# led-cpu-rev1.net
KiCad netlist of a schematic drawn in EAGLE
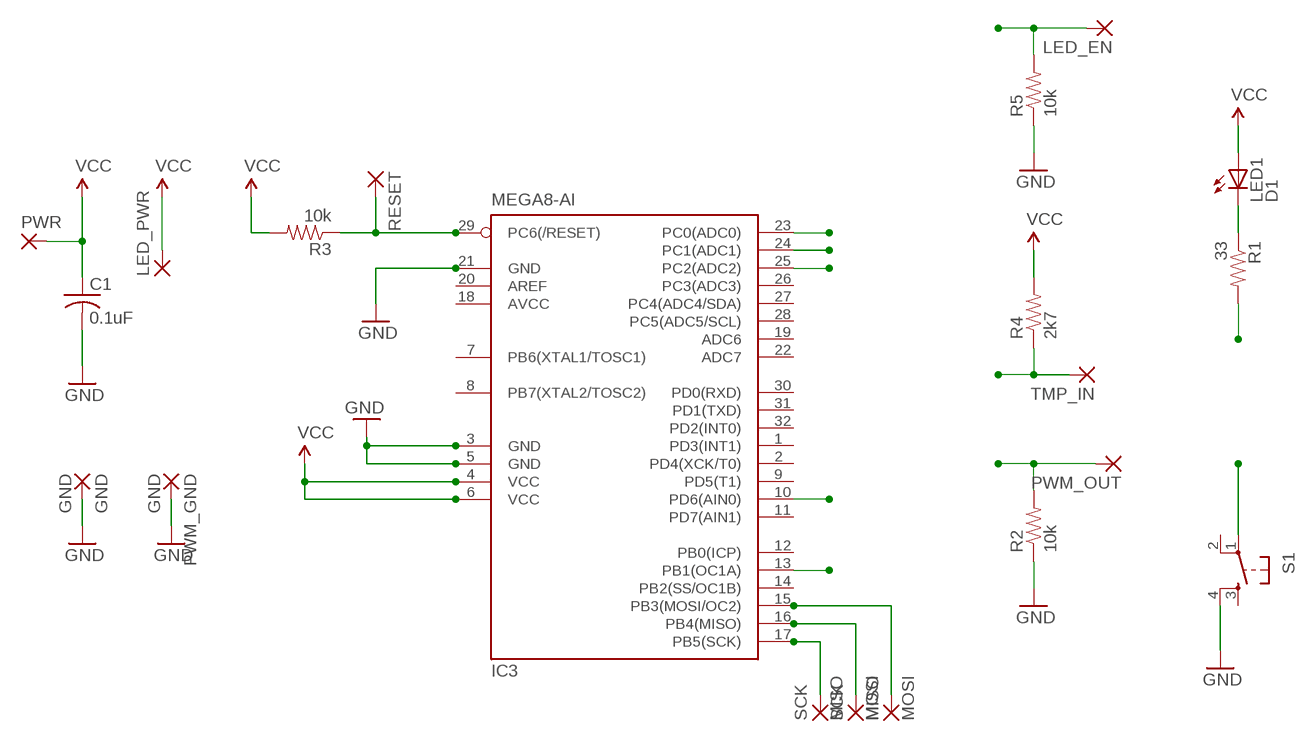
[diagram p0: schematic, sheet 1]

(export (version "E")
  (design (tool "Eeschema 10.0.6"))
  (components
    (comp (ref "C1")
      (value "0.1uF")
      (footprint "eagle-import:C1206")
      (libsource (lib "eagle-import") (part "C-USC1206"))
    )
    (comp (ref "GND")
      (value "GND")
      (footprint "eagle-import:SMD2,54-5,08")
      (libsource (lib "eagle-import") (part "SMD5"))
    )
    (comp (ref "IC3")
      (value "MEGA8-AI")
      (footprint "eagle-import:TQFP32-08")
      (fields (field (name "MPN") "ATMEGA8-16AU"))
      (libsource (lib "eagle-import") (part "MEGA8-AI"))
    )
    (comp (ref "LED1")
      (value "D1")
      (footprint "eagle-import:CHIPLED_1206")
      (libsource (lib "eagle-import") (part "LEDCHIPLED_1206"))
    )
    (comp (ref "LED_EN")
      (value "SMD5")
      (footprint "eagle-import:SMD2,54-5,08")
      (libsource (lib "eagle-import") (part "SMD5"))
    )
    (comp (ref "LED_PWR")
      (value "SMD5")
      (footprint "eagle-import:SMD2,54-5,08")
      (libsource (lib "eagle-import") (part "SMD5"))
    )
    (comp (ref "MISO")
      (value "MISO")
      (footprint "eagle-import:SMD1,27-2,54")
      (libsource (lib "eagle-import") (part "SMD2"))
    )
    (comp (ref "MOSI")
      (value "MOSI")
      (footprint "eagle-import:SMD1,27-2,54")
      (libsource (lib "eagle-import") (part "SMD2"))
    )
    (comp (ref "PWM_GND")
      (value "GND")
      (footprint "eagle-import:SMD2,54-5,08")
      (libsource (lib "eagle-import") (part "SMD5"))
    )
    (comp (ref "PWM_OUT")
      (value "SMD5")
      (footprint "eagle-import:SMD2,54-5,08")
      (libsource (lib "eagle-import") (part "SMD5"))
    )
    (comp (ref "PWR")
      (value "SMD5")
      (footprint "eagle-import:SMD2,54-5,08")
      (libsource (lib "eagle-import") (part "SMD5"))
    )
    (comp (ref "R1")
      (value "33")
      (footprint "eagle-import:1206")
      (libsource (lib "eagle-import") (part "RESISTOR1206"))
    )
    (comp (ref "R2")
      (value "10k")
      (footprint "eagle-import:1206")
      (libsource (lib "eagle-import") (part "RESISTOR1206"))
    )
    (comp (ref "R3")
      (value "10k")
      (footprint "eagle-import:1206")
      (libsource (lib "eagle-import") (part "RESISTOR1206"))
    )
    (comp (ref "R4")
      (value "2k7")
      (footprint "eagle-import:1206")
      (libsource (lib "eagle-import") (part "RESISTOR1206"))
    )
    (comp (ref "R5")
      (value "10k")
      (footprint "eagle-import:1206")
      (libsource (lib "eagle-import") (part "RESISTOR1206"))
    )
    (comp (ref "RESET")
      (value "SMD2")
      (footprint "eagle-import:SMD1,27-2,54")
      (libsource (lib "eagle-import") (part "SMD2"))
    )
    (comp (ref "S1")
      (value "TAC_SWITCHPTH")
      (footprint "eagle-import:TACTILE-PTH")
      (libsource (lib "eagle-import") (part "TAC_SWITCHPTH"))
    )
    (comp (ref "SCK")
      (value "SCK")
      (footprint "eagle-import:SMD1,27-2,54")
      (libsource (lib "eagle-import") (part "SMD2"))
    )
    (comp (ref "TMP_IN")
      (value "SMD5")
      (footprint "eagle-import:SMD2,54-5,08")
      (libsource (lib "eagle-import") (part "SMD5"))
    )
  )
  (nets
    (net (code "1") (name "/AVCC") (class "Default")
      (node (ref "IC3") (pin "18") (pinfunction "AVCC_18") (pintype "power_in"))
    )
    (net (code "2") (name "/LED_EN") (class "Default")
      (node (ref "IC3") (pin "25") (pinfunction "PC2(ADC2)_25") (pintype "bidirectional"))
      (node (ref "LED_EN") (pin "1") (pinfunction "P_1") (pintype "passive"))
      (node (ref "R5") (pin "2") (pinfunction "2_2") (pintype "passive"))
    )
    (net (code "3") (name "/PWM_OUT") (class "Default")
      (node (ref "IC3") (pin "10") (pinfunction "PD6(AIN0)_10") (pintype "bidirectional"))
      (node (ref "PWM_OUT") (pin "1") (pinfunction "P_1") (pintype "passive"))
      (node (ref "R2") (pin "2") (pinfunction "2_2") (pintype "passive"))
    )
    (net (code "4") (name "/PWR_LED") (class "Default")
      (node (ref "IC3") (pin "13") (pinfunction "PB1(OC1A)_13") (pintype "bidirectional"))
      (node (ref "R1") (pin "2") (pinfunction "2_2") (pintype "passive"))
    )
    (net (code "5") (name "/PWR_SW") (class "Default")
      (node (ref "IC3") (pin "24") (pinfunction "PC1(ADC1)_24") (pintype "bidirectional"))
      (node (ref "S1") (pin "1") (pinfunction "1_1") (pintype "passive"))
    )
    (net (code "6") (name "/TMP_IN") (class "Default")
      (node (ref "IC3") (pin "23") (pinfunction "PC0(ADC0)_23") (pintype "bidirectional"))
      (node (ref "R4") (pin "1") (pinfunction "1_1") (pintype "passive"))
      (node (ref "TMP_IN") (pin "1") (pinfunction "P_1") (pintype "passive"))
    )
    (net (code "7") (name "GND") (class "Default")
      (node (ref "C1") (pin "2") (pinfunction "2_2") (pintype "passive"))
      (node (ref "GND") (pin "1") (pinfunction "P_1") (pintype "passive"))
      (node (ref "IC3") (pin "21") (pinfunction "GND_21") (pintype "power_in"))
      (node (ref "IC3") (pin "3") (pinfunction "GND_3") (pintype "power_in"))
      (node (ref "IC3") (pin "5") (pinfunction "GND_5") (pintype "power_in"))
      (node (ref "PWM_GND") (pin "1") (pinfunction "P_1") (pintype "passive"))
      (node (ref "R2") (pin "1") (pinfunction "1_1") (pintype "passive"))
      (node (ref "R5") (pin "1") (pinfunction "1_1") (pintype "passive"))
      (node (ref "S1") (pin "4") (pinfunction "4_4") (pintype "passive"))
    )
    (net (code "8") (name "Net-(IC3-PB3(MOSI{slash}OC2))") (class "Default")
      (node (ref "IC3") (pin "15") (pinfunction "PB3(MOSI/OC2)_15") (pintype "bidirectional"))
      (node (ref "MOSI") (pin "1") (pinfunction "P_1") (pintype "passive"))
    )
    (net (code "9") (name "Net-(IC3-PB4(MISO))") (class "Default")
      (node (ref "IC3") (pin "16") (pinfunction "PB4(MISO)_16") (pintype "bidirectional"))
      (node (ref "MISO") (pin "1") (pinfunction "P_1") (pintype "passive"))
    )
    (net (code "10") (name "Net-(IC3-PB5(SCK))") (class "Default")
      (node (ref "IC3") (pin "17") (pinfunction "PB5(SCK)_17") (pintype "bidirectional"))
      (node (ref "SCK") (pin "1") (pinfunction "P_1") (pintype "passive"))
    )
    (net (code "11") (name "Net-(IC3-PC6({slash}RESET))") (class "Default")
      (node (ref "IC3") (pin "29") (pinfunction "PC6(/RESET)_29") (pintype "bidirectional"))
      (node (ref "R3") (pin "1") (pinfunction "1_1") (pintype "passive"))
      (node (ref "RESET") (pin "1") (pinfunction "P_1") (pintype "passive"))
    )
    (net (code "12") (name "Net-(LED1-PadC)") (class "Default")
      (node (ref "LED1") (pin "C") (pinfunction "C_C") (pintype "passive"))
      (node (ref "R1") (pin "1") (pinfunction "1_1") (pintype "passive"))
    )
    (net (code "13") (name "VCC") (class "Default")
      (node (ref "C1") (pin "1") (pinfunction "1_1") (pintype "passive"))
      (node (ref "IC3") (pin "4") (pinfunction "VCC_4") (pintype "power_in"))
      (node (ref "IC3") (pin "6") (pinfunction "VCC_6") (pintype "power_in"))
      (node (ref "LED1") (pin "A") (pinfunction "A_A") (pintype "passive"))
      (node (ref "LED_PWR") (pin "1") (pinfunction "P_1") (pintype "passive"))
      (node (ref "PWR") (pin "1") (pinfunction "P_1") (pintype "passive"))
      (node (ref "R3") (pin "2") (pinfunction "2_2") (pintype "passive"))
      (node (ref "R4") (pin "2") (pinfunction "2_2") (pintype "passive"))
    )
    (net (code "14") (name "unconnected-(IC3-ADC6-Pad19)") (class "Default")
      (node (ref "IC3") (pin "19") (pinfunction "ADC6_19") (pintype "bidirectional"))
    )
    (net (code "15") (name "unconnected-(IC3-ADC7-Pad22)") (class "Default")
      (node (ref "IC3") (pin "22") (pinfunction "ADC7_22") (pintype "bidirectional"))
    )
    (net (code "16") (name "unconnected-(IC3-AREF-Pad20)") (class "Default")
      (node (ref "IC3") (pin "20") (pinfunction "AREF_20") (pintype "passive"))
    )
    (net (code "17") (name "unconnected-(IC3-PB0(ICP)-Pad12)") (class "Default")
      (node (ref "IC3") (pin "12") (pinfunction "PB0(ICP)_12") (pintype "bidirectional"))
    )
    (net (code "18") (name "unconnected-(IC3-PB2(SS{slash}OC1B)-Pad14)") (class "Default")
      (node (ref "IC3") (pin "14") (pinfunction "PB2(SS/OC1B)_14") (pintype "bidirectional"))
    )
    (net (code "19") (name "unconnected-(IC3-PB6(XTAL1{slash}TOSC1)-Pad7)") (class "Default")
      (node (ref "IC3") (pin "7") (pinfunction "PB6(XTAL1/TOSC1)_7") (pintype "bidirectional"))
    )
    (net (code "20") (name "unconnected-(IC3-PB7(XTAL2{slash}TOSC2)-Pad8)") (class "Default")
      (node (ref "IC3") (pin "8") (pinfunction "PB7(XTAL2/TOSC2)_8") (pintype "bidirectional"))
    )
    (net (code "21") (name "unconnected-(IC3-PC3(ADC3)-Pad26)") (class "Default")
      (node (ref "IC3") (pin "26") (pinfunction "PC3(ADC3)_26") (pintype "bidirectional"))
    )
    (net (code "22") (name "unconnected-(IC3-PC4(ADC4{slash}SDA)-Pad27)") (class "Default")
      (node (ref "IC3") (pin "27") (pinfunction "PC4(ADC4/SDA)_27") (pintype "bidirectional"))
    )
    (net (code "23") (name "unconnected-(IC3-PC5(ADC5{slash}SCL)-Pad28)") (class "Default")
      (node (ref "IC3") (pin "28") (pinfunction "PC5(ADC5/SCL)_28") (pintype "bidirectional"))
    )
    (net (code "24") (name "unconnected-(IC3-PD0(RXD)-Pad30)") (class "Default")
      (node (ref "IC3") (pin "30") (pinfunction "PD0(RXD)_30") (pintype "bidirectional"))
    )
    (net (code "25") (name "unconnected-(IC3-PD1(TXD)-Pad31)") (class "Default")
      (node (ref "IC3") (pin "31") (pinfunction "PD1(TXD)_31") (pintype "bidirectional"))
    )
    (net (code "26") (name "unconnected-(IC3-PD2(INT0)-Pad32)") (class "Default")
      (node (ref "IC3") (pin "32") (pinfunction "PD2(INT0)_32") (pintype "bidirectional"))
    )
    (net (code "27") (name "unconnected-(IC3-PD3(INT1)-Pad1)") (class "Default")
      (node (ref "IC3") (pin "1") (pinfunction "PD3(INT1)_1") (pintype "bidirectional"))
    )
    (net (code "28") (name "unconnected-(IC3-PD4(XCK{slash}T0)-Pad2)") (class "Default")
      (node (ref "IC3") (pin "2") (pinfunction "PD4(XCK/T0)_2") (pintype "bidirectional"))
    )
    (net (code "29") (name "unconnected-(IC3-PD5(T1)-Pad9)") (class "Default")
      (node (ref "IC3") (pin "9") (pinfunction "PD5(T1)_9") (pintype "bidirectional"))
    )
    (net (code "30") (name "unconnected-(IC3-PD7(AIN1)-Pad11)") (class "Default")
      (node (ref "IC3") (pin "11") (pinfunction "PD7(AIN1)_11") (pintype "bidirectional"))
    )
    (net (code "31") (name "unconnected-(S1-Pad2)") (class "Default")
      (node (ref "S1") (pin "2") (pinfunction "2_2") (pintype "passive"))
    )
    (net (code "32") (name "unconnected-(S1-Pad3)") (class "Default")
      (node (ref "S1") (pin "3") (pinfunction "3_3") (pintype "passive"))
    )
  )
)
